# Sensors.net
KiCad netlist of a schematic drawn in Altium Designer
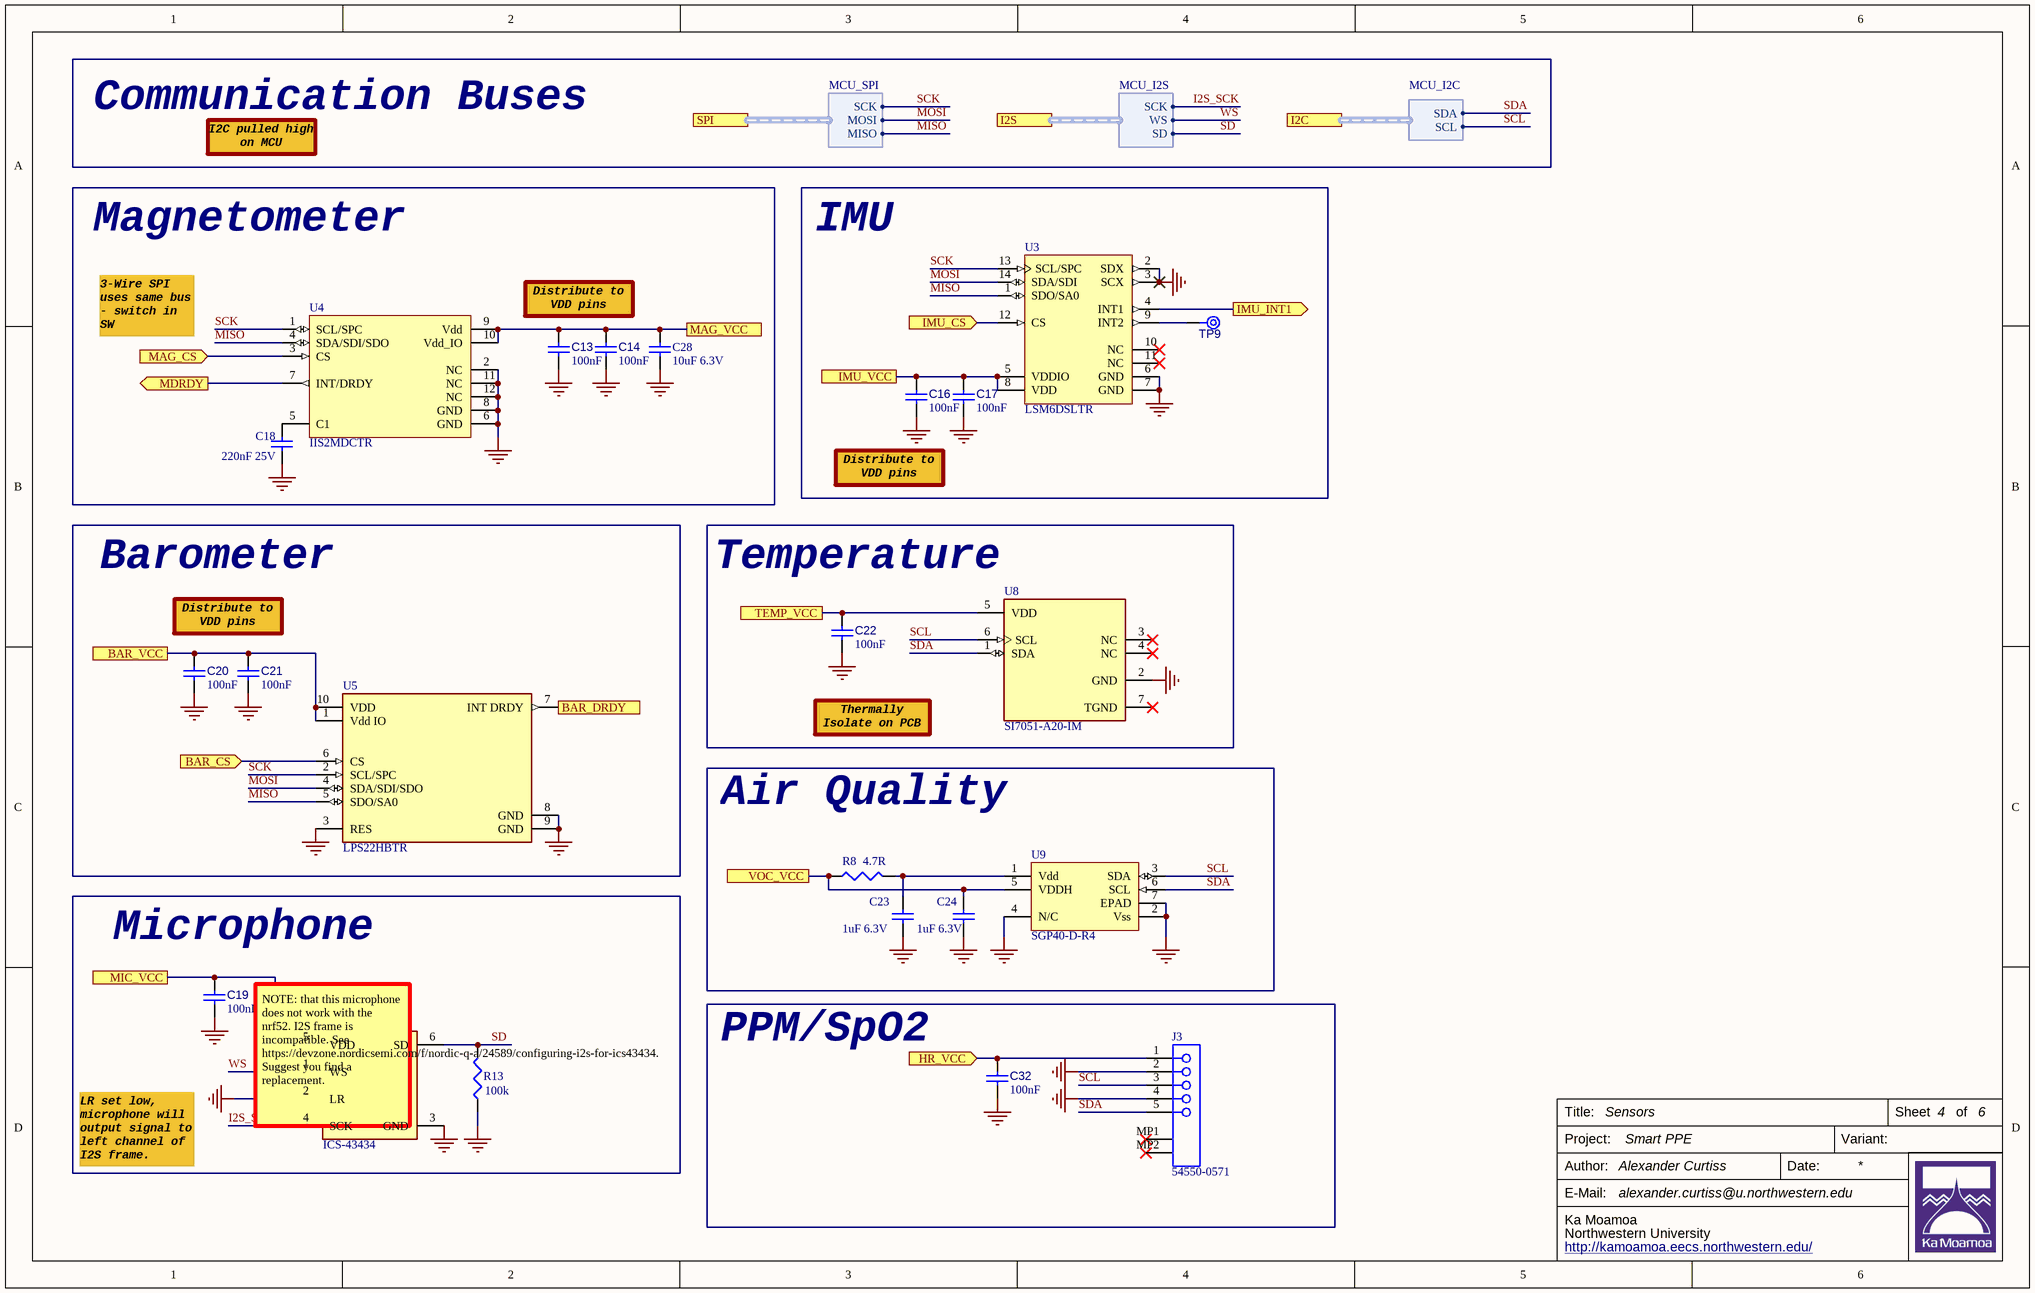
[diagram p0: Sensors.SchDoc]

(export (version "E")
  (design (tool "Eeschema 10.0.6"))
  (components
    (comp (ref "C13")
      (value "100nF")
      (footprint "CAPC0402(1005)60_L")
      (description "Chip Capacitor, 100nF +/-20%, 25V, 0402, Thickness 0.6 mm")
      (fields (field (name "TOLERANCE") "10%") (field (name "Comment") "Capacitor 100nF +/-20% 25V 0402"))
      (libsource (lib "Ka Moamoa") (part "CAP-NP-2"))
    )
    (comp (ref "C14")
      (value "100nF")
      (footprint "CAPC0402(1005)60_L")
      (description "Chip Capacitor, 100nF +/-20%, 25V, 0402, Thickness 0.6 mm")
      (fields (field (name "TOLERANCE") "10%") (field (name "Comment") "Capacitor 100nF +/-20% 25V 0402"))
      (libsource (lib "Ka Moamoa") (part "CAP-NP-2"))
    )
    (comp (ref "C16")
      (value "100nF")
      (footprint "CAPC0402(1005)60_L")
      (description "Chip Capacitor, 100nF +/-20%, 25V, 0402, Thickness 0.6 mm")
      (fields (field (name "TOLERANCE") "10%") (field (name "Comment") "Capacitor 100nF +/-20% 25V 0402"))
      (libsource (lib "Ka Moamoa") (part "CAP-NP-2"))
    )
    (comp (ref "C17")
      (value "100nF")
      (footprint "CAPC0402(1005)60_L")
      (description "Chip Capacitor, 100nF +/-20%, 25V, 0402, Thickness 0.6 mm")
      (fields (field (name "TOLERANCE") "10%") (field (name "Comment") "Capacitor 100nF +/-20% 25V 0402"))
      (libsource (lib "Ka Moamoa") (part "CAP-NP-2"))
    )
    (comp (ref "C18")
      (value "220nF 25V")
      (footprint "CAPC0603(1608)100_N")
      (description "CAP 220nF 25V ±10% 0603 (1608 Metric) Thickness 1mm SMD")
      (fields (field (name "TOLERANCE") "Â±10%"))
      (libsource (lib "Altium Content Vault") (part "CAP"))
    )
    (comp (ref "C19")
      (value "100nF")
      (footprint "CAPC0402(1005)60_L")
      (description "Chip Capacitor, 100nF +/-20%, 25V, 0402, Thickness 0.6 mm")
      (fields (field (name "TOLERANCE") "10%") (field (name "Comment") "Capacitor 100nF +/-20% 25V 0402"))
      (libsource (lib "Ka Moamoa") (part "CAP-NP-2"))
    )
    (comp (ref "C20")
      (value "100nF")
      (footprint "CAPC0402(1005)60_L")
      (description "Chip Capacitor, 100nF +/-20%, 25V, 0402, Thickness 0.6 mm")
      (fields (field (name "TOLERANCE") "10%") (field (name "Comment") "Capacitor 100nF +/-20% 25V 0402"))
      (libsource (lib "Ka Moamoa") (part "CAP-NP-2"))
    )
    (comp (ref "C21")
      (value "100nF")
      (footprint "CAPC0402(1005)60_L")
      (description "Chip Capacitor, 100nF +/-20%, 25V, 0402, Thickness 0.6 mm")
      (fields (field (name "TOLERANCE") "10%") (field (name "Comment") "Capacitor 100nF +/-20% 25V 0402"))
      (libsource (lib "Ka Moamoa") (part "CAP-NP-2"))
    )
    (comp (ref "C22")
      (value "100nF")
      (footprint "CAPC0402(1005)60_L")
      (description "Chip Capacitor, 100nF +/-20%, 25V, 0402, Thickness 0.6 mm")
      (fields (field (name "TOLERANCE") "10%") (field (name "Comment") "Capacitor 100nF +/-20% 25V 0402"))
      (libsource (lib "Ka Moamoa") (part "CAP-NP-2"))
    )
    (comp (ref "C23")
      (value "1uF 6.3V")
      (footprint "CAPC1005X55X25ML5T10")
      (description "Chip Capacitor, 1 uF, +/- 10%, 6.3 V, -55 to 85 degC, 1005 (0402 Metric), RoHS, Tape and Reel")
      (fields (field (name "TOLERANCE") "10%") (field (name "MANUFACTURER") "Yageo"))
      (libsource (lib "Altium Content Vault") (part "CAP-NP-2"))
    )
    (comp (ref "C24")
      (value "1uF 6.3V")
      (footprint "CAPC1005X55X25ML5T10")
      (description "Chip Capacitor, 1 uF, +/- 10%, 6.3 V, -55 to 85 degC, 1005 (0402 Metric), RoHS, Tape and Reel")
      (fields (field (name "TOLERANCE") "10%") (field (name "MANUFACTURER") "Yageo"))
      (libsource (lib "Altium Content Vault") (part "CAP-NP-2"))
    )
    (comp (ref "C28")
      (value "10uF 6.3V")
      (footprint "CAPC1608X90X35NL10T15")
      (fields (field (name "PART NUMBER") "GRM188R60J106ME47D") (field (name "MANUFACTURER") "Murata"))
      (libsource (lib "Altium Content Vault") (part "CAP"))
    )
    (comp (ref "C32")
      (value "100nF")
      (footprint "CAPC0402(1005)60_L")
      (description "Chip Capacitor, 100nF +/-20%, 25V, 0402, Thickness 0.6 mm")
      (fields (field (name "TOLERANCE") "10%") (field (name "Comment") "Capacitor 100nF +/-20% 25V 0402"))
      (libsource (lib "Ka Moamoa") (part "CAP-NP-2"))
    )
    (comp (ref "J3")
      (value "54550-0571")
      (footprint "MOLX-54550-0571")
      (fields (field (name "MANUFACTURER") "Molex"))
      (libsource (lib "Altium Content Vault") (part "MOLX-54550-0571"))
    )
    (comp (ref "MK1")
      (value "Mic_InvenSense_ICS-43434_eec")
      (footprint "InvenSense_ICS-43434_0")
      (description "MIC MEMS MULTI-MODE OMNI -26DB")
      (fields
        (field (name "PART NUMBER") "ICS-43434")
        (field (name "DIGIKEY PART NUMBER") "1428-1066-1-ND")
        (field (name "MANUFACTURER") "InvenSense")
      )
      (libsource (lib "Ka Moamoa") (part "Mic_InvenSense_ICS-43434_eec"))
    )
    (comp (ref "R8")
      (value "4.7R")
      (footprint "RESC1608X55X25NL10T15")
      (description "Resistor 4.7Ω 1% 0603")
      (fields (field (name "TOLERANCE") "1%"))
      (libsource (lib "Ka Moamoa") (part "RES"))
    )
    (comp (ref "R13")
      (value "100k")
      (footprint "RESC1608X55X25NL10T15")
      (description "Resistor 100kΩ 1% 0603")
      (fields (field (name "TOLERANCE") "1%"))
      (libsource (lib "Ka Moamoa") (part "RES"))
    )
    (comp (ref "TP9")
      (value "VSTOR")
      (footprint "TP06R")
      (description "0.6mm round test point")
      (libsource (lib "Ka Moamoa") (part "CMP-001-0001-4"))
    )
    (comp (ref "U3")
      (value "LSM6DSLTR")
      (footprint "STM-LGA-14_2500X3000X860")
      (fields (field (name "MANUFACTURER") "STMicroelectronics"))
      (libsource (lib "Altium Content Vault") (part "STM-LSM6DSLTR-LGA-14"))
    )
    (comp (ref "U4")
      (value "IIS2MDCTR")
      (footprint "LSM6DSLTR")
      (description "HIGH ACCURACY ULTRA-LOW-POWER 3-")
      (libsource (lib "Ka Moamoa") (part "IIS2MDCTR"))
    )
    (comp (ref "U5")
      (value "LPS22HBTR")
      (footprint "FP-HLGA-10L-8479831-0")
      (description "MEMS NANO PRESSURE SENSOR: 260-1")
      (fields
        (field (name "OCTOPART") "https://octopart.com/lps22hbtr-stmicroelectronics-51851131")
        (field (name "MANUFACTURER") "STMicroelectronics")
      )
      (libsource (lib "Altium Content Vault") (part "d4c28707ea3ba579869663dd93796c5"))
    )
    (comp (ref "U8")
      (value "SI7051-A20-IM")
      (footprint "FP-SI7051-A20-IM-MFG")
      (description "SENSOR DIGITAL -40C-125C 6DFN")
      (fields
        (field (name "MANUFACTURER") "Silicon Labs")
        (field (name "OCTOPART") "https://octopart.com/si7051-a20-im-silicon+labs-71522607")
      )
      (libsource (lib "Altium Content Vault") (part "cec00cf0f31483b0349f351f4a861df"))
    )
    (comp (ref "U9")
      (value "SGP40-D-R4")
      (footprint "SGP40-D-R4")
      (description "SGP40 Series 3.6 V 4 mA Indoor Air Quality Sensor for VOC Measurements - DFN-6")
      (libsource (lib "Ka Moamoa") (part "SGP40-D-R4"))
    )
  )
  (nets
    (net (code "4") (name "/BAR_CS") (class "Default")
      (node (ref "U5") (pin "6") (pinfunction "CS_6") (pintype "input"))
    )
    (net (code "5") (name "/BAR_DRDY") (class "Default")
      (node (ref "U5") (pin "7") (pinfunction "INT_DRDY_7") (pintype "output"))
    )
    (net (code "6") (name "/BAR_VCC") (class "Default")
      (node (ref "C20") (pin "1") (pinfunction "1_1") (pintype "passive"))
      (node (ref "C21") (pin "1") (pinfunction "1_1") (pintype "passive"))
      (node (ref "U5") (pin "1") (pinfunction "Vdd_IO_1") (pintype "power_in"))
      (node (ref "U5") (pin "10") (pinfunction "VDD_10") (pintype "power_in"))
    )
    (net (code "7") (name "/HR_VCC") (class "Default")
      (node (ref "C32") (pin "1") (pinfunction "1_1") (pintype "passive"))
      (node (ref "J3") (pin "1") (pinfunction "1_1") (pintype "passive"))
    )
    (net (code "8") (name "/I2S_SCK") (class "Default")
      (node (ref "MK1") (pin "4") (pinfunction "SCK_4") (pintype "passive"))
    )
    (net (code "9") (name "/IMU_CS") (class "Default")
      (node (ref "U3") (pin "12") (pinfunction "CS_12") (pintype "input"))
    )
    (net (code "10") (name "/IMU_INT1") (class "Default")
      (node (ref "U3") (pin "4") (pinfunction "INT1_4") (pintype "output"))
    )
    (net (code "11") (name "/IMU_VCC") (class "Default")
      (node (ref "C16") (pin "1") (pinfunction "1_1") (pintype "passive"))
      (node (ref "C17") (pin "1") (pinfunction "1_1") (pintype "passive"))
      (node (ref "U3") (pin "5") (pinfunction "VDDIO_5") (pintype "power_in"))
      (node (ref "U3") (pin "8") (pinfunction "VDD_8") (pintype "power_in"))
    )
    (net (code "12") (name "/MAG_CS") (class "Default")
      (node (ref "U4") (pin "3") (pinfunction "CS_3") (pintype "input"))
    )
    (net (code "13") (name "/MAG_VCC") (class "Default")
      (node (ref "C13") (pin "1") (pinfunction "1_1") (pintype "passive"))
      (node (ref "C14") (pin "1") (pinfunction "1_1") (pintype "passive"))
      (node (ref "C28") (pin "2") (pinfunction "2_2") (pintype "passive"))
      (node (ref "U4") (pin "10") (pinfunction "Vdd_IO_10") (pintype "power_in"))
      (node (ref "U4") (pin "9") (pinfunction "Vdd_9") (pintype "power_in"))
    )
    (net (code "14") (name "/MDRDY") (class "Default")
      (node (ref "U4") (pin "7") (pinfunction "INT/DRDY_7") (pintype "output"))
    )
    (net (code "15") (name "/MIC_VCC") (class "Default")
      (node (ref "C19") (pin "1") (pinfunction "1_1") (pintype "passive"))
      (node (ref "MK1") (pin "5") (pinfunction "VDD_5") (pintype "passive"))
    )
    (net (code "16") (name "/MISO") (class "Default")
      (node (ref "U3") (pin "1") (pinfunction "SDO/SA0_1") (pintype "bidirectional"))
      (node (ref "U4") (pin "4") (pinfunction "SDA/SDI/SDO_4") (pintype "bidirectional"))
      (node (ref "U5") (pin "5") (pinfunction "SDO/SA0_5") (pintype "bidirectional"))
    )
    (net (code "17") (name "/MOSI") (class "Default")
      (node (ref "U3") (pin "14") (pinfunction "SDA/SDI_14") (pintype "bidirectional"))
      (node (ref "U5") (pin "4") (pinfunction "SDA/SDI/SDO_4") (pintype "bidirectional"))
    )
    (net (code "18") (name "/SCK") (class "Default")
      (node (ref "U3") (pin "13") (pinfunction "SCL/SPC_13") (pintype "input"))
      (node (ref "U4") (pin "1") (pinfunction "SCL/SPC_1") (pintype "bidirectional"))
      (node (ref "U5") (pin "2") (pinfunction "SCL/SPC_2") (pintype "input"))
    )
    (net (code "19") (name "/SCL") (class "Default")
      (node (ref "J3") (pin "3") (pinfunction "3_3") (pintype "passive"))
      (node (ref "U8") (pin "6") (pinfunction "SCL_6") (pintype "input"))
      (node (ref "U9") (pin "3") (pinfunction "SDA_3") (pintype "bidirectional"))
    )
    (net (code "20") (name "/SD") (class "Default")
      (node (ref "MK1") (pin "6") (pinfunction "SD_6") (pintype "passive"))
      (node (ref "R13") (pin "2") (pinfunction "2_2") (pintype "passive"))
    )
    (net (code "21") (name "/SDA") (class "Default")
      (node (ref "J3") (pin "5") (pinfunction "5_5") (pintype "passive"))
      (node (ref "U8") (pin "1") (pinfunction "SDA_1") (pintype "bidirectional"))
      (node (ref "U9") (pin "6") (pinfunction "SCL_6") (pintype "input"))
    )
    (net (code "22") (name "/TEMP_VCC") (class "Default")
      (node (ref "C22") (pin "1") (pinfunction "1_1") (pintype "passive"))
      (node (ref "U8") (pin "5") (pinfunction "VDD_5") (pintype "power_in"))
    )
    (net (code "23") (name "/VOC_VCC") (class "Default")
      (node (ref "C24") (pin "2") (pinfunction "2_2") (pintype "passive"))
      (node (ref "R8") (pin "1") (pinfunction "1_1") (pintype "passive"))
      (node (ref "U9") (pin "5") (pinfunction "VDDH_5") (pintype "power_in"))
    )
    (net (code "24") (name "/WS") (class "Default")
      (node (ref "MK1") (pin "1") (pinfunction "WS_1") (pintype "passive"))
    )
    (net (code "28") (name "GND") (class "Default")
      (node (ref "C13") (pin "2") (pinfunction "2_2") (pintype "passive"))
      (node (ref "C14") (pin "2") (pinfunction "2_2") (pintype "passive"))
      (node (ref "C16") (pin "2") (pinfunction "2_2") (pintype "passive"))
      (node (ref "C17") (pin "2") (pinfunction "2_2") (pintype "passive"))
      (node (ref "C18") (pin "1") (pinfunction "1_1") (pintype "passive"))
      (node (ref "C19") (pin "2") (pinfunction "2_2") (pintype "passive"))
      (node (ref "C20") (pin "2") (pinfunction "2_2") (pintype "passive"))
      (node (ref "C21") (pin "2") (pinfunction "2_2") (pintype "passive"))
      (node (ref "C22") (pin "2") (pinfunction "2_2") (pintype "passive"))
      (node (ref "C23") (pin "1") (pinfunction "1_1") (pintype "passive"))
      (node (ref "C24") (pin "1") (pinfunction "1_1") (pintype "passive"))
      (node (ref "C28") (pin "1") (pinfunction "1_1") (pintype "passive"))
      (node (ref "C32") (pin "2") (pinfunction "2_2") (pintype "passive"))
      (node (ref "J3") (pin "2") (pinfunction "2_2") (pintype "passive"))
      (node (ref "J3") (pin "4") (pinfunction "4_4") (pintype "passive"))
      (node (ref "MK1") (pin "2") (pinfunction "LR_2") (pintype "passive"))
      (node (ref "MK1") (pin "3") (pinfunction "GND_3") (pintype "passive"))
      (node (ref "R13") (pin "1") (pinfunction "1_1") (pintype "passive"))
      (node (ref "U3") (pin "2") (pinfunction "SDX_2") (pintype "output"))
      (node (ref "U3") (pin "3") (pinfunction "SCX_3") (pintype "output"))
      (node (ref "U3") (pin "6") (pinfunction "GND_6") (pintype "power_in"))
      (node (ref "U3") (pin "7") (pinfunction "GND_7") (pintype "power_in"))
      (node (ref "U4") (pin "11") (pinfunction "NC_11") (pintype "passive"))
      (node (ref "U4") (pin "12") (pinfunction "NC_12") (pintype "passive"))
      (node (ref "U4") (pin "2") (pinfunction "NC_2") (pintype "passive"))
      (node (ref "U4") (pin "6") (pinfunction "GND_6") (pintype "power_in"))
      (node (ref "U4") (pin "8") (pinfunction "GND_8") (pintype "power_in"))
      (node (ref "U5") (pin "3") (pinfunction "RES_3") (pintype "passive"))
      (node (ref "U5") (pin "8") (pinfunction "GND_8") (pintype "power_in"))
      (node (ref "U5") (pin "9") (pinfunction "GND_9") (pintype "power_in"))
      (node (ref "U8") (pin "2") (pinfunction "GND_2") (pintype "power_in"))
      (node (ref "U9") (pin "2") (pinfunction "Vss_2") (pintype "power_in"))
      (node (ref "U9") (pin "4") (pinfunction "N/C_4") (pintype "power_in"))
      (node (ref "U9") (pin "7") (pinfunction "EPAD_7") (pintype "passive"))
    )
    (net (code "29") (name "Net-(TP9-TP)") (class "Default")
      (node (ref "TP9") (pin "1") (pinfunction "TP_1") (pintype "passive"))
      (node (ref "U3") (pin "9") (pinfunction "INT2_9") (pintype "output"))
    )
    (net (code "30") (name "Net-(U4-C1)") (class "Default")
      (node (ref "C18") (pin "2") (pinfunction "2_2") (pintype "passive"))
      (node (ref "U4") (pin "5") (pinfunction "C1_5") (pintype "passive"))
    )
    (net (code "31") (name "Net-(U9-Vdd)") (class "Default")
      (node (ref "C23") (pin "2") (pinfunction "2_2") (pintype "passive"))
      (node (ref "R8") (pin "2") (pinfunction "2_2") (pintype "passive"))
      (node (ref "U9") (pin "1") (pinfunction "Vdd_1") (pintype "power_in"))
    )
    (net (code "32") (name "unconnected-(J3-PadMP1)") (class "Default")
      (node (ref "J3") (pin "MP1") (pinfunction "MP1_MP1") (pintype "passive+no_connect"))
    )
    (net (code "33") (name "unconnected-(J3-PadMP2)") (class "Default")
      (node (ref "J3") (pin "MP2") (pinfunction "MP2_MP2") (pintype "passive+no_connect"))
    )
    (net (code "34") (name "unconnected-(U3-NC-Pad10)") (class "Default")
      (node (ref "U3") (pin "10") (pinfunction "NC_10") (pintype "passive+no_connect"))
    )
    (net (code "35") (name "unconnected-(U3-NC-Pad11)") (class "Default")
      (node (ref "U3") (pin "11") (pinfunction "NC_11") (pintype "passive+no_connect"))
    )
    (net (code "36") (name "unconnected-(U8-NC-Pad3)") (class "Default")
      (node (ref "U8") (pin "3") (pinfunction "NC_3") (pintype "passive+no_connect"))
    )
    (net (code "37") (name "unconnected-(U8-NC-Pad4)") (class "Default")
      (node (ref "U8") (pin "4") (pinfunction "NC_4") (pintype "passive+no_connect"))
    )
    (net (code "38") (name "unconnected-(U8-TGND-Pad7)") (class "Default")
      (node (ref "U8") (pin "7") (pinfunction "TGND_7") (pintype "power_in+no_connect"))
    )
  )
)
